# PBL44_Sch.net
KiCad netlist of a schematic drawn in Altium Designer
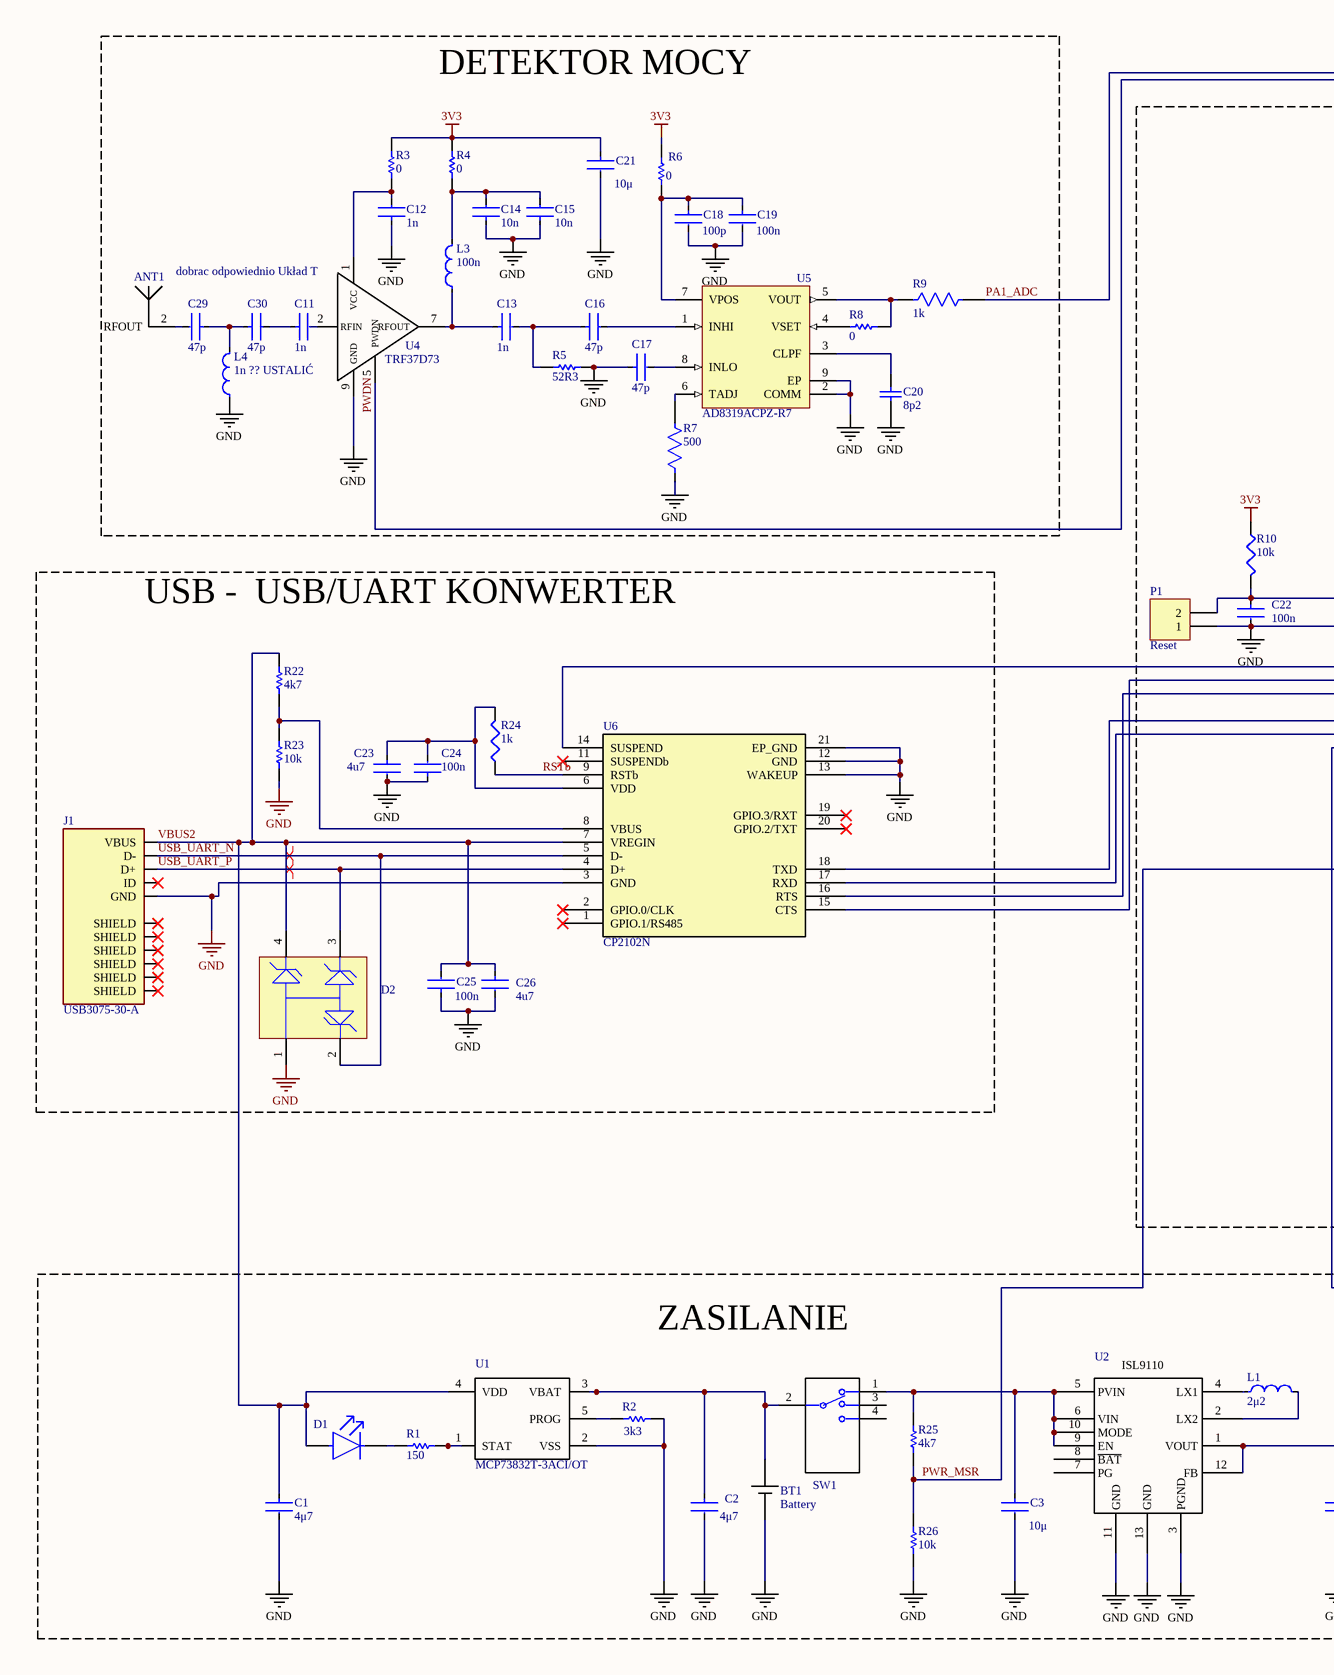
[diagram p0: PBL44_Sch.SchDoc, left]
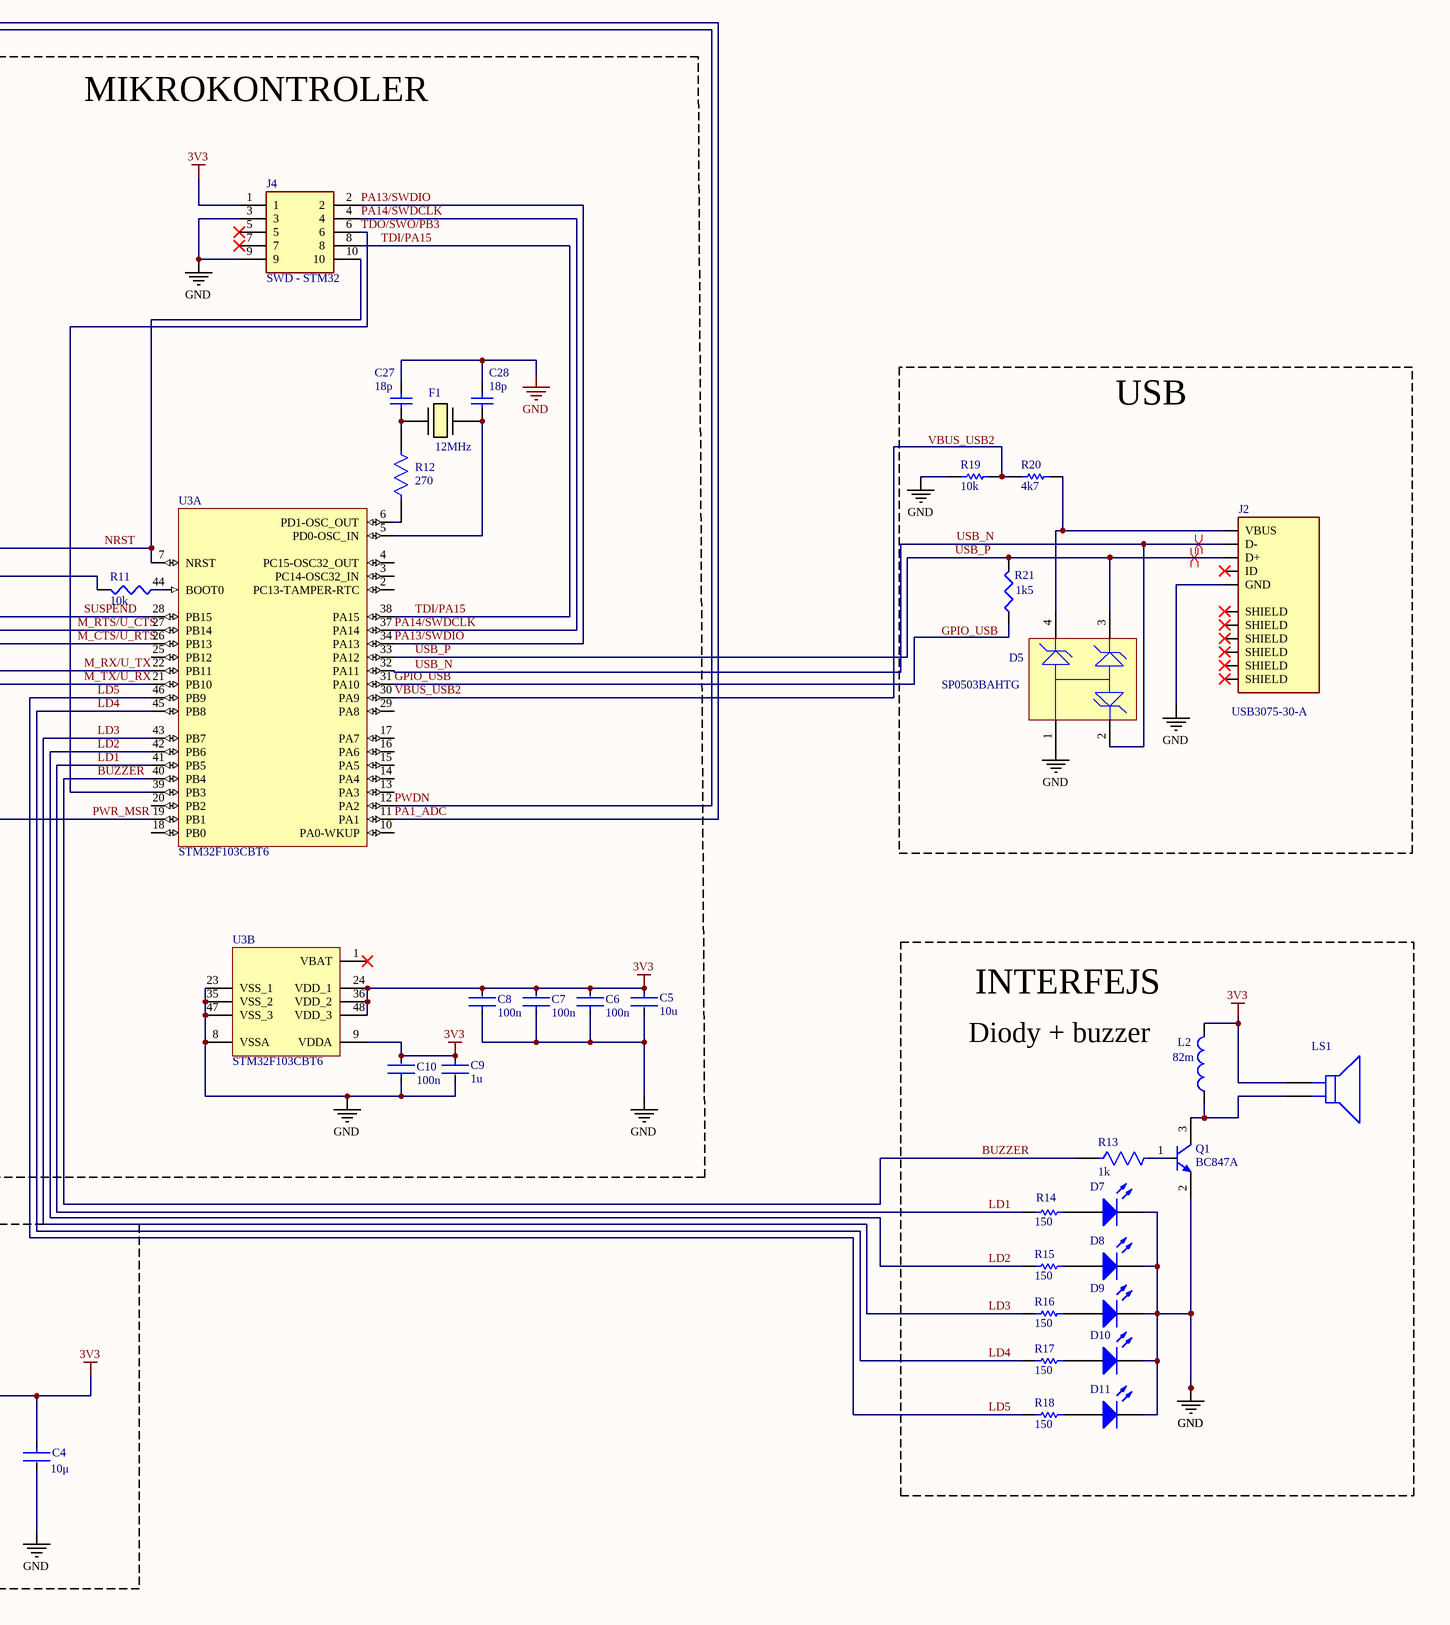
[diagram p1: PBL44_Sch.SchDoc, right]

(export (version "E")
  (design (tool "Eeschema 10.0.6"))
  (components
    (comp (ref "ANT1")
      (value "2195852-1")
      (footprint "Antena:Antena")
      (libsource (lib "Antena") (part "2195852-1"))
    )
    (comp (ref "BT1")
      (value "Battery")
      (footprint "PBL4_PCB_Lib:HDR1X2")
      (libsource (lib "Schlib_KM_PBL4") (part "KM_Battery_One_Cell"))
    )
    (comp (ref "C1")
      (value "~")
      (footprint "FP-C2012-125-0_2-IPC_B")
      (description "Multilayer Ceramic Capacitors 4.7μF ±10% 50V X5R SMD 0805")
      (fields
        (field (name "VOLTAGE") "50V")
        (field (name "CAPACITANCE") "4μ7")
        (field (name "TOLERANCE") "10%")
      )
      (libsource (lib "Altium Content Vault") (part "b4654b650e69147ec39a6b967a45e02"))
    )
    (comp (ref "C2")
      (value "~")
      (footprint "FP-C2012-125-0_2-IPC_B")
      (description "Multilayer Ceramic Capacitors 4.7μF ±10% 50V X5R SMD 0805")
      (fields
        (field (name "VOLTAGE") "50V")
        (field (name "CAPACITANCE") "4μ7")
        (field (name "TOLERANCE") "10%")
      )
      (libsource (lib "Altium Content Vault") (part "b4654b650e69147ec39a6b967a45e02"))
    )
    (comp (ref "C3")
      (value "10μ")
      (footprint "FP-C0805C-DG-MFG")
      (description "CAP CER 10UF 10V X5R 0805")
      (fields (field (name "TOLERANCE") "10%") (field (name "MANUFACTURER PART NUMBER") "C0805C106K8PACTU"))
      (libsource (lib "Altium Content Vault") (part "11868f565c42a9108669ba33697ecf6"))
    )
    (comp (ref "C4")
      (value "10μ")
      (footprint "FP-C0805C-DG-MFG")
      (description "CAP CER 10UF 10V X5R 0805")
      (fields (field (name "TOLERANCE") "10%") (field (name "MANUFACTURER PART NUMBER") "C0805C106K8PACTU"))
      (libsource (lib "Altium Content Vault") (part "11868f565c42a9108669ba33697ecf6"))
    )
    (comp (ref "C5")
      (value "10u")
      (footprint "FP-C0805C-DN-MFG")
      (description "CAP CER 47PF 100V 5% NP0 0805")
      (fields
        (field (name "MANUFACTURER") "KEMET")
        (field (name "OCTOPART") "https://octopart.com/c0805c470j1gactu-kemet-9138638")
      )
      (libsource (lib "Altium Content Vault") (part "b4654b650e69147ec39a6b967a45e02"))
    )
    (comp (ref "C6")
      (value "C0603C103K1RACTU")
      (footprint "FP-C0603C-CF-MFG")
      (description "CAP CER 10000PF 100V X7R 0603")
      (fields
        (field (name "MANUFACTURER") "KEMET")
        (field (name "CAPACITANCE") "100n")
        (field (name "OCTOPART") "https://octopart.com/c0603c103k1ractu-kemet-134140")
      )
      (libsource (lib "Altium Content Vault") (part "b4654b650e69147ec39a6b967a45e02"))
    )
    (comp (ref "C7")
      (value "C0603C103K1RACTU")
      (footprint "FP-C0603C-CF-MFG")
      (description "CAP CER 10000PF 100V X7R 0603")
      (fields
        (field (name "MANUFACTURER") "KEMET")
        (field (name "CAPACITANCE") "100n")
        (field (name "OCTOPART") "https://octopart.com/c0603c103k1ractu-kemet-134140")
      )
      (libsource (lib "Altium Content Vault") (part "b4654b650e69147ec39a6b967a45e02"))
    )
    (comp (ref "C8")
      (value "C0603C103K1RACTU")
      (footprint "FP-C0603C-CF-MFG")
      (description "CAP CER 10000PF 100V X7R 0603")
      (fields
        (field (name "MANUFACTURER") "KEMET")
        (field (name "CAPACITANCE") "100n")
        (field (name "OCTOPART") "https://octopart.com/c0603c103k1ractu-kemet-134140")
      )
      (libsource (lib "Altium Content Vault") (part "b4654b650e69147ec39a6b967a45e02"))
    )
    (comp (ref "C9")
      (value "1u")
      (footprint "FP-C0805C-DN-MFG")
      (description "CAP CER 47PF 100V 5% NP0 0805")
      (fields
        (field (name "MANUFACTURER") "KEMET")
        (field (name "OCTOPART") "https://octopart.com/c0805c470j1gactu-kemet-9138638")
      )
      (libsource (lib "Altium Content Vault") (part "b4654b650e69147ec39a6b967a45e02"))
    )
    (comp (ref "C10")
      (value "C0603C103K1RACTU")
      (footprint "FP-C0603C-CF-MFG")
      (description "CAP CER 10000PF 100V X7R 0603")
      (fields
        (field (name "MANUFACTURER") "KEMET")
        (field (name "CAPACITANCE") "100n")
        (field (name "OCTOPART") "https://octopart.com/c0603c103k1ractu-kemet-134140")
      )
      (libsource (lib "Altium Content Vault") (part "b4654b650e69147ec39a6b967a45e02"))
    )
    (comp (ref "C11")
      (value "06035C102KAT2A")
      (footprint "FP-0603-L_1_6_0_15-W_0_81-IPC_A")
      (description "General Purpose Ceramic Capacitor, 0603, 1nF, 10%, X7R, 15%, 50V")
      (fields
        (field (name "CAPACITANCE") "1n")
        (field (name "VOLTAGE") "50V")
        (field (name "TOLERANCE") "10%")
      )
      (libsource (lib "Altium Content Vault") (part "02cd4be3c70576c341d710602a673aa"))
    )
    (comp (ref "C12")
      (value "06035C102KAT2A")
      (footprint "FP-0603-L_1_6_0_15-W_0_81-IPC_A")
      (description "General Purpose Ceramic Capacitor, 0603, 1nF, 10%, X7R, 15%, 50V")
      (fields
        (field (name "CAPACITANCE") "1n")
        (field (name "VOLTAGE") "50V")
        (field (name "TOLERANCE") "10%")
      )
      (libsource (lib "Altium Content Vault") (part "02cd4be3c70576c341d710602a673aa"))
    )
    (comp (ref "C13")
      (value "06035C102KAT2A")
      (footprint "FP-0603-L_1_6_0_15-W_0_81-IPC_A")
      (description "General Purpose Ceramic Capacitor, 0603, 1nF, 10%, X7R, 15%, 50V")
      (fields
        (field (name "CAPACITANCE") "1n")
        (field (name "VOLTAGE") "50V")
        (field (name "TOLERANCE") "10%")
      )
      (libsource (lib "Altium Content Vault") (part "02cd4be3c70576c341d710602a673aa"))
    )
    (comp (ref "C14")
      (value "C0603C103K1RACTU")
      (footprint "FP-C0603C-CF-MFG")
      (description "CAP CER 10000PF 100V X7R 0603")
      (fields
        (field (name "MANUFACTURER") "KEMET")
        (field (name "CAPACITANCE") "10n")
        (field (name "OCTOPART") "https://octopart.com/c0603c103k1ractu-kemet-134140")
      )
      (libsource (lib "Altium Content Vault") (part "b4654b650e69147ec39a6b967a45e02"))
    )
    (comp (ref "C15")
      (value "C0603C103K1RACTU")
      (footprint "FP-C0603C-CF-MFG")
      (description "CAP CER 10000PF 100V X7R 0603")
      (fields
        (field (name "MANUFACTURER") "KEMET")
        (field (name "CAPACITANCE") "10n")
        (field (name "OCTOPART") "https://octopart.com/c0603c103k1ractu-kemet-134140")
      )
      (libsource (lib "Altium Content Vault") (part "b4654b650e69147ec39a6b967a45e02"))
    )
    (comp (ref "C16")
      (value "47p")
      (footprint "FP-C0805C-DN-MFG")
      (description "CAP CER 47PF 100V 5% NP0 0805")
      (fields
        (field (name "MANUFACTURER") "KEMET")
        (field (name "OCTOPART") "https://octopart.com/c0805c470j1gactu-kemet-9138638")
      )
      (libsource (lib "Altium Content Vault") (part "b4654b650e69147ec39a6b967a45e02"))
    )
    (comp (ref "C17")
      (value "47p")
      (footprint "FP-C0805C-DN-MFG")
      (description "CAP CER 47PF 100V 5% NP0 0805")
      (fields
        (field (name "MANUFACTURER") "KEMET")
        (field (name "OCTOPART") "https://octopart.com/c0805c470j1gactu-kemet-9138638")
      )
      (libsource (lib "Altium Content Vault") (part "b4654b650e69147ec39a6b967a45e02"))
    )
    (comp (ref "C18")
      (value "C0603C104K5RACTU")
      (footprint "FP-C0603C-CF-MFG")
      (description "CAP CER 0.1UF 50V X7R 0603")
      (fields
        (field (name "TOLERANCE") "0.1")
        (field (name "MANUFACTURER") "KEMET")
        (field (name "CAPACITANCE") "100p")
      )
      (libsource (lib "Altium Content Vault") (part "b4654b650e69147ec39a6b967a45e02"))
    )
    (comp (ref "C19")
      (value "C0603C104K5RACTU")
      (footprint "FP-C0603C-CF-MFG")
      (description "CAP CER 0.1UF 50V X7R 0603")
      (fields
        (field (name "TOLERANCE") "0.1")
        (field (name "MANUFACTURER") "KEMET")
        (field (name "CAPACITANCE") "100n")
      )
      (libsource (lib "Altium Content Vault") (part "b4654b650e69147ec39a6b967a45e02"))
    )
    (comp (ref "C20")
      (value "06035J8R2BBSTR")
      (footprint "CAPC1608X73X35ML10T15")
      (fields (field (name "MANUFACTURER") "AVX Interconnect / Elco") (field (name "CAPACITANCE") "8p2"))
      (libsource (lib "Altium Content Vault") (part "CAP"))
    )
    (comp (ref "C21")
      (value "10μ")
      (footprint "FP-C0805C-DG-MFG")
      (description "CAP CER 10UF 10V X5R 0805")
      (fields (field (name "TOLERANCE") "10%") (field (name "MANUFACTURER PART NUMBER") "C0805C106K8PACTU"))
      (libsource (lib "Altium Content Vault") (part "11868f565c42a9108669ba33697ecf6"))
    )
    (comp (ref "C22")
      (value "~")
      (footprint "FP-C2012-125-0_2-IPC_B")
      (description "Multilayer Ceramic Capacitors 4.7μF ±10% 50V X5R SMD 0805")
      (fields
        (field (name "VOLTAGE") "50V")
        (field (name "CAPACITANCE") "100n")
        (field (name "TOLERANCE") "10%")
      )
      (libsource (lib "Altium Content Vault") (part "b4654b650e69147ec39a6b967a45e02"))
    )
    (comp (ref "C23")
      (value "4u7")
      (footprint "FP-C0805C-DN-MFG")
      (description "CAP CER 47PF 100V 5% NP0 0805")
      (fields
        (field (name "MANUFACTURER") "KEMET")
        (field (name "OCTOPART") "https://octopart.com/c0805c470j1gactu-kemet-9138638")
      )
      (libsource (lib "Altium Content Vault") (part "b4654b650e69147ec39a6b967a45e02"))
    )
    (comp (ref "C24")
      (value "C0603C103K1RACTU")
      (footprint "FP-C0603C-CF-MFG")
      (description "CAP CER 10000PF 100V X7R 0603")
      (fields
        (field (name "MANUFACTURER") "KEMET")
        (field (name "CAPACITANCE") "100n")
        (field (name "OCTOPART") "https://octopart.com/c0603c103k1ractu-kemet-134140")
      )
      (libsource (lib "Altium Content Vault") (part "b4654b650e69147ec39a6b967a45e02"))
    )
    (comp (ref "C25")
      (value "C0603C103K1RACTU")
      (footprint "FP-C0603C-CF-MFG")
      (description "CAP CER 10000PF 100V X7R 0603")
      (fields
        (field (name "MANUFACTURER") "KEMET")
        (field (name "CAPACITANCE") "100n")
        (field (name "OCTOPART") "https://octopart.com/c0603c103k1ractu-kemet-134140")
      )
      (libsource (lib "Altium Content Vault") (part "b4654b650e69147ec39a6b967a45e02"))
    )
    (comp (ref "C26")
      (value "4u7")
      (footprint "FP-C0805C-DN-MFG")
      (description "CAP CER 47PF 100V 5% NP0 0805")
      (fields
        (field (name "MANUFACTURER") "KEMET")
        (field (name "OCTOPART") "https://octopart.com/c0805c470j1gactu-kemet-9138638")
      )
      (libsource (lib "Altium Content Vault") (part "b4654b650e69147ec39a6b967a45e02"))
    )
    (comp (ref "C27")
      (value "06035J8R2BBSTR")
      (footprint "CAPC1608X73X35ML10T15")
      (fields (field (name "MANUFACTURER") "AVX Interconnect / Elco") (field (name "CAPACITANCE") "18p"))
      (libsource (lib "Altium Content Vault") (part "CAP"))
    )
    (comp (ref "C28")
      (value "06035J8R2BBSTR")
      (footprint "CAPC1608X73X35ML10T15")
      (fields (field (name "MANUFACTURER") "AVX Interconnect / Elco") (field (name "CAPACITANCE") "18p"))
      (libsource (lib "Altium Content Vault") (part "CAP"))
    )
    (comp (ref "C29")
      (value "C0603C104K5RACTU")
      (footprint "FP-C0603C-CF-MFG")
      (description "CAP CER 0.1UF 50V X7R 0603")
      (fields
        (field (name "TOLERANCE") "0.1")
        (field (name "MANUFACTURER") "KEMET")
        (field (name "CAPACITANCE") "47p")
      )
      (libsource (lib "Altium Content Vault") (part "b4654b650e69147ec39a6b967a45e02"))
    )
    (comp (ref "C30")
      (value "C0603C104K5RACTU")
      (footprint "FP-C0603C-CF-MFG")
      (description "CAP CER 0.1UF 50V X7R 0603")
      (fields
        (field (name "TOLERANCE") "0.1")
        (field (name "MANUFACTURER") "KEMET")
        (field (name "CAPACITANCE") "47p")
      )
      (libsource (lib "Altium Content Vault") (part "b4654b650e69147ec39a6b967a45e02"))
    )
    (comp (ref "D1")
      (value "LTST-C190GKT")
      (footprint "FP-LTST-C190GKT-MFG")
      (description "LED GREEN CLEAR CHIP SMD")
      (fields (field (name "VOLTAGE") "2V"))
      (libsource (lib "Altium Content Vault") (part "8706943c75ba83719d021d2fdc84c58"))
    )
    (comp (ref "D2")
      (value "SP0503BAHTG")
      (footprint "LFUS-SOT143-4_V")
      (description "TVS Diode Array, 30 pF, 30 KV, -40 to 85 degC, 4-Pin SOT143, RoHS, Tape and Reel")
      (fields (field (name "MANUFACTURER") "Littelfuse"))
      (libsource (lib "Altium Content Vault") (part "LFUS-SP0503BAHTG-SOT143-4"))
    )
    (comp (ref "D5")
      (value "SP0503BAHTG")
      (footprint "LFUS-SOT143-4_V")
      (description "TVS Diode Array, 30 pF, 30 KV, -40 to 85 degC, 4-Pin SOT143, RoHS, Tape and Reel")
      (fields (field (name "MANUFACTURER") "Littelfuse"))
      (libsource (lib "Altium Content Vault") (part "LFUS-SP0503BAHTG-SOT143-4"))
    )
    (comp (ref "D7")
      (value "151051RS11000")
      (footprint "Type 5mm")
      (description "THT LED round mono-color color lens, WL-TMRW, Red")
      (fields (field (name "MANUFACTURER") "Wuerth Elektronik"))
      (libsource (lib "Altium Content Vault") (part "WE-LED_K1A2-2"))
    )
    (comp (ref "D8")
      (value "151051RS11000")
      (footprint "Type 5mm")
      (description "THT LED round mono-color color lens, WL-TMRW, Red")
      (fields (field (name "MANUFACTURER") "Wuerth Elektronik"))
      (libsource (lib "Altium Content Vault") (part "WE-LED_K1A2-2"))
    )
    (comp (ref "D9")
      (value "151051RS11000")
      (footprint "Type 5mm")
      (description "THT LED round mono-color color lens, WL-TMRW, Red")
      (fields (field (name "MANUFACTURER") "Wuerth Elektronik"))
      (libsource (lib "Altium Content Vault") (part "WE-LED_K1A2-2"))
    )
    (comp (ref "D10")
      (value "151051RS11000")
      (footprint "Type 5mm")
      (description "THT LED round mono-color color lens, WL-TMRW, Red")
      (fields (field (name "MANUFACTURER") "Wuerth Elektronik"))
      (libsource (lib "Altium Content Vault") (part "WE-LED_K1A2-2"))
    )
    (comp (ref "D11")
      (value "151051RS11000")
      (footprint "Type 5mm")
      (description "THT LED round mono-color color lens, WL-TMRW, Red")
      (fields (field (name "MANUFACTURER") "Wuerth Elektronik"))
      (libsource (lib "Altium Content Vault") (part "WE-LED_K1A2-2"))
    )
    (comp (ref "F1")
      (value "12MHz")
      (footprint "AltiumLibraryElements:HC/49US-(AT49)_1")
      (fields
        (field (name "MANUFACTURER_PART_NUMBER") "ABLS-12.000MHZ-B4-T")
        (field (name "MOUSER PART NUMBER") "815-ABLS-12.0M-T")
      )
      (libsource (lib "AltiumLibraryElements") (part "ABLS-12.000MHZ-B4-T"))
    )
    (comp (ref "J1")
      (value "USB3075-30-A")
      (footprint "PBL4_PCB_Lib:GCT_USB3075-30-A")
      (description "USB - micro B USB 2.0 Receptacle Connector 5 Position Surface Mount, Right Angle; Through Hole")
      (fields
        (field (name "MF") "Global Connector Technology")
        (field (name "DIGI-KEY_PART_NUMBER") "2073-USB3075-30-ACT-ND")
      )
      (libsource (lib "USB3075-30-A") (part "USB3075-30-A"))
    )
    (comp (ref "J2")
      (value "USB3075-30-A")
      (footprint "PBL4_PCB_Lib:GCT_USB3075-30-A")
      (description "USB - micro B USB 2.0 Receptacle Connector 5 Position Surface Mount, Right Angle; Through Hole")
      (fields
        (field (name "MF") "Global Connector Technology")
        (field (name "DIGI-KEY_PART_NUMBER") "2073-USB3075-30-ACT-ND")
      )
      (libsource (lib "") (part "USB3075-30-A_1"))
    )
    (comp (ref "J4")
      (value "SWD - STM32")
      (footprint "PBL4_PCB_Lib:322110030000")
      (description "Connector")
      (fields (field (name "MANUFACTURER_PART_NUMBER") "3221-10-0300-00"))
      (libsource (lib "AltiumLibraryElements") (part "3221-10-0300-00"))
    )
    (comp (ref "L1")
      (value "NRS5040T2R2NMGJ")
      (footprint "FP-NR5040-H_4_1-MFG")
      (description "SMD Power Inductors 2.2uH ±30% 3.7A 28.6mΩ")
      (fields (field (name "TOLERANCE") "20%") (field (name "INDUCTANCE") "2μ2"))
      (libsource (lib "Altium Content Vault") (part "725321dda6339637d4d059423bc1c3c"))
    )
    (comp (ref "L2")
      (value "7447471104")
      (footprint "WE-TIS 1111")
      (description "Shielded Radial Leaded Wire Wound Inductor WE-TIS, L=100000 µH")
      (fields (field (name "INDUCTANCE") "82m") (field (name "MANUFACTURER") "Wuerth Elektronik"))
      (libsource (lib "Altium Content Vault") (part "PAS-IND-INDUCTOR-2"))
    )
    (comp (ref "L3")
      (value "LQW18ANR10G00D")
      (footprint "FP-LQW18AN_00-MFG")
      (description "Wire Wound RF Inductor 100nH ±2% 220mA 0.68Ω 0603 (1608)")
      (fields (field (name "TOLERANCE") "2%") (field (name "INDUCTANCE") "100n"))
      (libsource (lib "Altium Content Vault") (part "725321dda6339637d4d059423bc1c3c"))
    )
    (comp (ref "L4")
      (value "LQW18ANR10G00D")
      (footprint "FP-LQW18AN_00-MFG")
      (description "Wire Wound RF Inductor 100nH ±2% 220mA 0.68Ω 0603 (1608)")
      (fields (field (name "TOLERANCE") "2%") (field (name "INDUCTANCE") "1n ?? USTALIĆ"))
      (libsource (lib "Altium Content Vault") (part "725321dda6339637d4d059423bc1c3c"))
    )
    (comp (ref "LS1")
      (value "7BB-20-6L0")
      (footprint "FP-7BB-20-6L0-MFG")
      (description "BUZZER ELEMENT STD 6.3KHZ")
      (libsource (lib "Components - 08.04.22 - 12.49") (part "CMP-06202-000037-1"))
    )
    (comp (ref "P1")
      (value "Reset")
      (footprint "HDR1X2")
      (description "Header, 2-Pin")
      (fields (field (name "PUBLISHER") "Altium Limited"))
      (libsource (lib "Miscellaneous Connectors") (part "Header 2"))
    )
    (comp (ref "Q1")
      (value "BC847A")
      (footprint "INF-SOT23_M")
      (description "NPN Silicon AF Transistor, 45 V VCEO, 100 mA IC, SOT23, Reel, Green")
      (fields (field (name "MANUFACTURER") "Infineon"))
      (libsource (lib "Altium Content Vault") (part "INF-BJTNPN-BEC-3"))
    )
    (comp (ref "R1")
      (value "ERJ-3EKF4700V")
      (footprint "RESC1608X55X30ML15T15")
      (description "Chip Resistor, 470 Ohm, +/- 1%, 0.1 W, -55 to 155 degC, 0603 (1608 Metric), RoHS, Tape and Reel")
      (fields (field (name "MANUFACTURER") "Panasonic") (field (name "RESISTANCE") "150"))
      (libsource (lib "Altium Content Vault") (part "RES-2"))
    )
    (comp (ref "R2")
      (value "RC0805FR-073K3L")
      (footprint "RESC2013X60X35ML10T20")
      (description "Chip Resistor, 3.3 KOhm, +/- 1%, 0.125 W, -55 to 155 degC, 0805 (2012 Metric), RoHS, Tape and Reel")
      (fields
        (field (name "RESISTANCE") "3k3")
        (field (name "TOLERANCE") "1%")
        (field (name "MANUFACTURER") "Yageo")
      )
      (libsource (lib "Altium Content Vault") (part "RES-2"))
    )
    (comp (ref "R3")
      (value "0")
      (footprint "RESC1609X50X30NL8T20")
      (description "Chip Resistor, 0 Ohm, Jumper, 100 mW, -55 to 155 degC, 0603 (1608 Metric), RoHS, Tape and Reel")
      (fields
        (field (name "MANUFACTURER") "Vishay Semiconductor")
        (field (name "Comment") "CRCW06030000Z0EA")
      )
      (libsource (lib "Altium Content Vault") (part "RES-2"))
    )
    (comp (ref "R4")
      (value "0")
      (footprint "RESC1609X50X30NL8T20")
      (description "Chip Resistor, 0 Ohm, Jumper, 100 mW, -55 to 155 degC, 0603 (1608 Metric), RoHS, Tape and Reel")
      (fields
        (field (name "MANUFACTURER") "Vishay Semiconductor")
        (field (name "Comment") "CRCW06030000Z0EA")
      )
      (libsource (lib "Altium Content Vault") (part "RES-2"))
    )
    (comp (ref "R5")
      (value "ERJ-3EKF52R3V")
      (footprint "RESC1608X55X30ML15T15")
      (fields (field (name "MANUFACTURER") "Panasonic") (field (name "RESISTANCE") "52R3"))
      (libsource (lib "Altium Content Vault") (part "RES"))
    )
    (comp (ref "R6")
      (value "CRCW06030000Z0EA")
      (footprint "RESC1609X50X30NL8T20")
      (description "Chip Resistor, 0 Ohm, Jumper, 100 mW, -55 to 155 degC, 0603 (1608 Metric), RoHS, Tape and Reel")
      (fields (field (name "MANUFACTURER") "Vishay Semiconductor") (field (name "RESISTANCE") "0"))
      (libsource (lib "Altium Content Vault") (part "RES-2"))
    )
    (comp (ref "R7")
      (value "MCT06030D5000BP100")
      (footprint "FP-MCT0603-MFG")
      (description "RES SMD 100 OHM 1% 1/8W 0603")
      (fields (field (name "RESISTANCE") "500") (field (name "TOLERANCE") "0.1%"))
      (libsource (lib "Altium Content Vault") (part "1029c3af85768c4190bb7ad29bc67b5"))
    )
    (comp (ref "R8")
      (value "CRCW06030000Z0EA")
      (footprint "RESC1609X50X30NL8T20")
      (description "Chip Resistor, 0 Ohm, Jumper, 100 mW, -55 to 155 degC, 0603 (1608 Metric), RoHS, Tape and Reel")
      (fields (field (name "MANUFACTURER") "Vishay Semiconductor") (field (name "RESISTANCE") "0"))
      (libsource (lib "Altium Content Vault") (part "RES-2"))
    )
    (comp (ref "R9")
      (value "CRCW06031K00FKEA")
      (footprint "FP-CRCW0603-e3-MFG")
      (description "RES Thick Film, 1kΩ, 1%, 0.1W, 100ppm/°C, 0603")
      (fields (field (name "TOLERANCE") "1%") (field (name "RESISTANCE") "1k"))
      (libsource (lib "Altium Content Vault") (part "1029c3af85768c4190bb7ad29bc67b5"))
    )
    (comp (ref "R10")
      (value "10k")
      (footprint "J1-0603")
      (description "Resistor")
      (fields (field (name "Comment") "Res3") (field (name "PUBLISHER") "Altium Limited"))
      (libsource (lib "Miscellaneous Devices") (part "Res3"))
    )
    (comp (ref "R11")
      (value "10k")
      (footprint "J1-0603")
      (description "Resistor")
      (fields (field (name "Comment") "Res3") (field (name "PUBLISHER") "Altium Limited"))
      (libsource (lib "Miscellaneous Devices") (part "Res3"))
    )
    (comp (ref "R12")
      (value "CRCW06031K00FKEA")
      (footprint "FP-CRCW0603-e3-MFG")
      (description "RES Thick Film, 1kΩ, 1%, 0.1W, 100ppm/°C, 0603")
      (fields (field (name "TOLERANCE") "1%") (field (name "RESISTANCE") "270"))
      (libsource (lib "Altium Content Vault") (part "1029c3af85768c4190bb7ad29bc67b5"))
    )
    (comp (ref "R13")
      (value "CRCW06031K00FKEA")
      (footprint "FP-CRCW0603-e3-MFG")
      (description "RES Thick Film, 1kΩ, 1%, 0.1W, 100ppm/°C, 0603")
      (fields (field (name "TOLERANCE") "1%") (field (name "RESISTANCE") "1k"))
      (libsource (lib "Altium Content Vault") (part "1029c3af85768c4190bb7ad29bc67b5"))
    )
    (comp (ref "R14")
      (value "ERJ-3EKF4700V")
      (footprint "RESC1608X55X30ML15T15")
      (description "Chip Resistor, 470 Ohm, +/- 1%, 0.1 W, -55 to 155 degC, 0603 (1608 Metric), RoHS, Tape and Reel")
      (fields (field (name "MANUFACTURER") "Panasonic") (field (name "RESISTANCE") "150"))
      (libsource (lib "Altium Content Vault") (part "RES-2"))
    )
    (comp (ref "R15")
      (value "ERJ-3EKF4700V")
      (footprint "RESC1608X55X30ML15T15")
      (description "Chip Resistor, 470 Ohm, +/- 1%, 0.1 W, -55 to 155 degC, 0603 (1608 Metric), RoHS, Tape and Reel")
      (fields (field (name "MANUFACTURER") "Panasonic") (field (name "RESISTANCE") "150"))
      (libsource (lib "Altium Content Vault") (part "RES-2"))
    )
    (comp (ref "R16")
      (value "ERJ-3EKF4700V")
      (footprint "RESC1608X55X30ML15T15")
      (description "Chip Resistor, 470 Ohm, +/- 1%, 0.1 W, -55 to 155 degC, 0603 (1608 Metric), RoHS, Tape and Reel")
      (fields (field (name "MANUFACTURER") "Panasonic") (field (name "RESISTANCE") "150"))
      (libsource (lib "Altium Content Vault") (part "RES-2"))
    )
    (comp (ref "R17")
      (value "ERJ-3EKF4700V")
      (footprint "RESC1608X55X30ML15T15")
      (description "Chip Resistor, 470 Ohm, +/- 1%, 0.1 W, -55 to 155 degC, 0603 (1608 Metric), RoHS, Tape and Reel")
      (fields (field (name "MANUFACTURER") "Panasonic") (field (name "RESISTANCE") "150"))
      (libsource (lib "Altium Content Vault") (part "RES-2"))
    )
    (comp (ref "R18")
      (value "ERJ-3EKF4700V")
      (footprint "RESC1608X55X30ML15T15")
      (description "Chip Resistor, 470 Ohm, +/- 1%, 0.1 W, -55 to 155 degC, 0603 (1608 Metric), RoHS, Tape and Reel")
      (fields (field (name "MANUFACTURER") "Panasonic") (field (name "RESISTANCE") "150"))
      (libsource (lib "Altium Content Vault") (part "RES-2"))
    )
    (comp (ref "R19")
      (value "RC0805FR-073K3L")
      (footprint "RESC2013X60X35ML10T20")
      (description "Chip Resistor, 3.3 KOhm, +/- 1%, 0.125 W, -55 to 155 degC, 0805 (2012 Metric), RoHS, Tape and Reel")
      (fields
        (field (name "RESISTANCE") "10k")
        (field (name "TOLERANCE") "1%")
        (field (name "MANUFACTURER") "Yageo")
      )
      (libsource (lib "Altium Content Vault") (part "RES-2"))
    )
    (comp (ref "R20")
      (value "RC0805FR-073K3L")
      (footprint "RESC2013X60X35ML10T20")
      (description "Chip Resistor, 3.3 KOhm, +/- 1%, 0.125 W, -55 to 155 degC, 0805 (2012 Metric), RoHS, Tape and Reel")
      (fields
        (field (name "RESISTANCE") "4k7")
        (field (name "TOLERANCE") "1%")
        (field (name "MANUFACTURER") "Yageo")
      )
      (libsource (lib "Altium Content Vault") (part "RES-2"))
    )
    (comp (ref "R21")
      (value "1k5")
      (footprint "J1-0603")
      (description "Resistor")
      (fields (field (name "Comment") "Res3") (field (name "PUBLISHER") "Altium Limited"))
      (libsource (lib "Miscellaneous Devices") (part "Res3"))
    )
    (comp (ref "R22")
      (value "RC0805FR-073K3L")
      (footprint "RESC2013X60X35ML10T20")
      (description "Chip Resistor, 3.3 KOhm, +/- 1%, 0.125 W, -55 to 155 degC, 0805 (2012 Metric), RoHS, Tape and Reel")
      (fields
        (field (name "RESISTANCE") "4k7")
        (field (name "TOLERANCE") "1%")
        (field (name "MANUFACTURER") "Yageo")
      )
      (libsource (lib "Altium Content Vault") (part "RES-2"))
    )
    (comp (ref "R23")
      (value "RC0805FR-073K3L")
      (footprint "RESC2013X60X35ML10T20")
      (description "Chip Resistor, 3.3 KOhm, +/- 1%, 0.125 W, -55 to 155 degC, 0805 (2012 Metric), RoHS, Tape and Reel")
      (fields
        (field (name "RESISTANCE") "10k")
        (field (name "TOLERANCE") "1%")
        (field (name "MANUFACTURER") "Yageo")
      )
      (libsource (lib "Altium Content Vault") (part "RES-2"))
    )
    (comp (ref "R24")
      (value "1k")
      (footprint "J1-0603")
      (description "Resistor")
      (fields (field (name "Comment") "Res3") (field (name "PUBLISHER") "Altium Limited"))
      (libsource (lib "Miscellaneous Devices") (part "Res3"))
    )
    (comp (ref "R25")
      (value "RC0805FR-073K3L")
      (footprint "RESC2013X60X35ML10T20")
      (description "Chip Resistor, 3.3 KOhm, +/- 1%, 0.125 W, -55 to 155 degC, 0805 (2012 Metric), RoHS, Tape and Reel")
      (fields
        (field (name "RESISTANCE") "4k7")
        (field (name "TOLERANCE") "1%")
        (field (name "MANUFACTURER") "Yageo")
      )
      (libsource (lib "Altium Content Vault") (part "RES-2"))
    )
    (comp (ref "R26")
      (value "RC0805FR-073K3L")
      (footprint "RESC2013X60X35ML10T20")
      (description "Chip Resistor, 3.3 KOhm, +/- 1%, 0.125 W, -55 to 155 degC, 0805 (2012 Metric), RoHS, Tape and Reel")
      (fields
        (field (name "RESISTANCE") "10k")
        (field (name "TOLERANCE") "1%")
        (field (name "MANUFACTURER") "Yageo")
      )
      (libsource (lib "Altium Content Vault") (part "RES-2"))
    )
    (comp (ref "SW1")
      (value "MHS133G04")
      (footprint "PBL4_PCB_Lib:Alcoswitch_MHS133G04_0")
      (libsource (lib "Switch_Alcoswitch_MHS133G04_eec") (part "MHS133G04"))
    )
    (comp (ref "U1")
      (value "MCP73832T-3ACI/OT")
      (footprint "SOT-23-OT5_M")
      (libsource (lib "Components - 19.03.22 - 12.24") (part "CMP-0133-00135-1"))
    )
    (comp (ref "U2")
      (value "ISL9110")
      (footprint "KM_L12.3x3C")
      (description "L12.3x3C")
      (libsource (lib "Schlib_KM_PBL4") (part "KM_ISL9110"))
    )
    (comp (ref "U3")
      (value "STM32F103CBT6")
      (footprint "STM-LQFP48_L")
      (libsource (lib "Altium Content Vault") (part "MC-ARM-STM32F103X8_B-SQ48"))
    )
    (comp (ref "U4")
      (value "TRF37D73")
      (footprint "JD_WSON-8")
      (libsource (lib "JD_Projekt") (part "JD_TRF37D73_WSON-8"))
    )
    (comp (ref "U5")
      (value "AD8319ACPZ-R7")
      (footprint "ADI-CP-8-1_L")
      (description "1 MHz to 10 GHz, 45 dB Log Detector/Controller, 6ns Response Time, CP-8-1, Pb-Free, 3000 Reel")
      (libsource (lib "Components - 10.04.22 - 23.39") (part "CMP-0284-00069-1"))
    )
    (comp (ref "U6")
      (value "CP2102N")
      (footprint "PBL4_PCB_Lib:ZW_QFN20")
      (libsource (lib "PBL4_ZW") (part "ZW_CP2102N-A02-GQFN20R"))
    )
  )
  (nets
    (net (code "1") (name "/BUZZER") (class "Default")
      (node (ref "R13") (pin "1") (pinfunction "1_1") (pintype "passive"))
      (node (ref "U3") (pin "40") (pinfunction "PB4_40") (pintype "bidirectional"))
    )
    (net (code "2") (name "/GPIO_USB") (class "Default")
      (node (ref "R21") (pin "1") (pinfunction "1_1") (pintype "passive"))
      (node (ref "U3") (pin "31") (pinfunction "PA10_31") (pintype "bidirectional"))
    )
    (net (code "3") (name "/LD1") (class "Default")
      (node (ref "R14") (pin "1") (pinfunction "1_1") (pintype "passive"))
      (node (ref "U3") (pin "41") (pinfunction "PB5_41") (pintype "bidirectional"))
    )
    (net (code "4") (name "/LD2") (class "Default")
      (node (ref "R15") (pin "1") (pinfunction "1_1") (pintype "passive"))
      (node (ref "U3") (pin "42") (pinfunction "PB6_42") (pintype "bidirectional"))
    )
    (net (code "5") (name "/LD3") (class "Default")
      (node (ref "R16") (pin "1") (pinfunction "1_1") (pintype "passive"))
      (node (ref "U3") (pin "43") (pinfunction "PB7_43") (pintype "bidirectional"))
    )
    (net (code "6") (name "/LD4") (class "Default")
      (node (ref "R17") (pin "1") (pinfunction "1_1") (pintype "passive"))
      (node (ref "U3") (pin "45") (pinfunction "PB8_45") (pintype "bidirectional"))
    )
    (net (code "7") (name "/LD5") (class "Default")
      (node (ref "R18") (pin "1") (pinfunction "1_1") (pintype "passive"))
      (node (ref "U3") (pin "46") (pinfunction "PB9_46") (pintype "bidirectional"))
    )
    (net (code "8") (name "/M_CTS{slash}U_RTS") (class "Default")
      (node (ref "U3") (pin "26") (pinfunction "PB13_26") (pintype "bidirectional"))
      (node (ref "U6") (pin "16") (pinfunction "RTS_16") (pintype "passive"))
    )
    (net (code "9") (name "/M_RTS{slash}U_CTS") (class "Default")
      (node (ref "U3") (pin "27") (pinfunction "PB14_27") (pintype "bidirectional"))
      (node (ref "U6") (pin "15") (pinfunction "CTS_15") (pintype "passive"))
    )
    (net (code "10") (name "/M_RX{slash}U_TX") (class "Default")
      (node (ref "U3") (pin "22") (pinfunction "PB11_22") (pintype "bidirectional"))
      (node (ref "U6") (pin "18") (pinfunction "TXD_18") (pintype "passive"))
    )
    (net (code "11") (name "/M_TX{slash}U_RX") (class "Default")
      (node (ref "U3") (pin "21") (pinfunction "PB10_21") (pintype "bidirectional"))
      (node (ref "U6") (pin "17") (pinfunction "RXD_17") (pintype "passive"))
    )
    (net (code "12") (name "/NRST") (class "Default")
      (node (ref "C22") (pin "1") (pinfunction "1_1") (pintype "passive"))
      (node (ref "J4") (pin "10") (pinfunction "10_10") (pintype "passive"))
      (node (ref "P1") (pin "2") (pinfunction "2_2") (pintype "passive"))
      (node (ref "R10") (pin "2") (pinfunction "2_2") (pintype "passive"))
      (node (ref "U3") (pin "7") (pinfunction "NRST_7") (pintype "bidirectional"))
    )
    (net (code "13") (name "/PA1_ADC") (class "Default")
      (node (ref "R9") (pin "2") (pinfunction "2_2") (pintype "passive"))
      (node (ref "U3") (pin "11") (pinfunction "PA1_11") (pintype "bidirectional"))
    )
    (net (code "14") (name "/PA13{slash}SWDIO") (class "Default")
      (node (ref "J4") (pin "2") (pinfunction "2_2") (pintype "passive"))
      (node (ref "U3") (pin "34") (pinfunction "PA13_34") (pintype "bidirectional"))
    )
    (net (code "15") (name "/PA14{slash}SWDCLK") (class "Default")
      (node (ref "J4") (pin "4") (pinfunction "4_4") (pintype "passive"))
      (node (ref "U3") (pin "37") (pinfunction "PA14_37") (pintype "bidirectional"))
    )
    (net (code "16") (name "/PWDN") (class "Default")
      (node (ref "U3") (pin "12") (pinfunction "PA2_12") (pintype "bidirectional"))
      (node (ref "U4") (pin "5") (pinfunction "PWDN_5") (pintype "passive"))
    )
    (net (code "17") (name "/PWR_MSR") (class "Default")
      (node (ref "R25") (pin "2") (pinfunction "2_2") (pintype "passive"))
      (node (ref "R26") (pin "1") (pinfunction "1_1") (pintype "passive"))
      (node (ref "U3") (pin "19") (pinfunction "PB1_19") (pintype "bidirectional"))
    )
    (net (code "18") (name "/RSTb") (class "Default")
      (node (ref "R24") (pin "2") (pinfunction "2_2") (pintype "passive"))
      (node (ref "U6") (pin "9") (pinfunction "RSTb_9") (pintype "passive"))
    )
    (net (code "19") (name "/SUSPEND") (class "Default")
      (node (ref "U3") (pin "28") (pinfunction "PB15_28") (pintype "bidirectional"))
      (node (ref "U6") (pin "14") (pinfunction "SUSPEND_14") (pintype "passive"))
    )
    (net (code "20") (name "/TDI{slash}PA15") (class "Default")
      (node (ref "J4") (pin "8") (pinfunction "8_8") (pintype "passive"))
      (node (ref "U3") (pin "38") (pinfunction "PA15_38") (pintype "bidirectional"))
    )
    (net (code "21") (name "/TDO{slash}SWO{slash}PB3") (class "Default")
      (node (ref "J4") (pin "6") (pinfunction "6_6") (pintype "passive"))
      (node (ref "U3") (pin "39") (pinfunction "PB3_39") (pintype "bidirectional"))
    )
    (net (code "22") (name "/USB_N") (class "Default")
      (node (ref "D5") (pin "2") (pinfunction "2_2") (pintype "passive"))
      (node (ref "J2") (pin "2") (pinfunction "D-_2") (pintype "bidirectional"))
      (node (ref "U3") (pin "32") (pinfunction "PA11_32") (pintype "bidirectional"))
    )
    (net (code "23") (name "/USB_P") (class "Default")
      (node (ref "D5") (pin "3") (pinfunction "3_3") (pintype "passive"))
      (node (ref "J2") (pin "3") (pinfunction "D+_3") (pintype "bidirectional"))
      (node (ref "R21") (pin "2") (pinfunction "2_2") (pintype "passive"))
      (node (ref "U3") (pin "33") (pinfunction "PA12_33") (pintype "bidirectional"))
    )
    (net (code "24") (name "/USB_UART_N") (class "Default")
      (node (ref "D2") (pin "2") (pinfunction "2_2") (pintype "passive"))
      (node (ref "J1") (pin "2") (pinfunction "D-_2") (pintype "bidirectional"))
      (node (ref "U6") (pin "5") (pinfunction "D-_5") (pintype "passive"))
    )
    (net (code "25") (name "/USB_UART_P") (class "Default")
      (node (ref "D2") (pin "3") (pinfunction "3_3") (pintype "passive"))
      (node (ref "J1") (pin "3") (pinfunction "D+_3") (pintype "bidirectional"))
      (node (ref "U6") (pin "4") (pinfunction "D+_4") (pintype "passive"))
    )
    (net (code "26") (name "/VBUS2") (class "Default")
      (node (ref "C1") (pin "1") (pinfunction "1_1") (pintype "passive"))
      (node (ref "C25") (pin "2") (pinfunction "2_2") (pintype "passive"))
      (node (ref "C26") (pin "1") (pinfunction "1_1") (pintype "passive"))
      (node (ref "D1") (pin "2") (pinfunction "A_2") (pintype "passive"))
      (node (ref "D2") (pin "4") (pinfunction "4_4") (pintype "passive"))
      (node (ref "J1") (pin "1") (pinfunction "VBUS_1") (pintype "power_in"))
      (node (ref "R22") (pin "2") (pinfunction "2_2") (pintype "passive"))
      (node (ref "U1") (pin "4") (pinfunction "VDD_4") (pintype "power_in"))
      (node (ref "U6") (pin "7") (pinfunction "VREGIN_7") (pintype "passive"))
    )
    (net (code "27") (name "/VBUS_USB2") (class "Default")
      (node (ref "R19") (pin "1") (pinfunction "1_1") (pintype "passive"))
      (node (ref "R20") (pin "2") (pinfunction "2_2") (pintype "passive"))
      (node (ref "U3") (pin "30") (pinfunction "PA9_30") (pintype "bidirectional"))
    )
    (net (code "28") (name "3V3") (class "Default")
      (node (ref "C10") (pin "2") (pinfunction "2_2") (pintype "passive"))
      (node (ref "C21") (pin "1") (pinfunction "1_1") (pintype "passive"))
      (node (ref "C4") (pin "1") (pinfunction "1_1") (pintype "passive"))
      (node (ref "C5") (pin "1") (pinfunction "1_1") (pintype "passive"))
      (node (ref "C6") (pin "2") (pinfunction "2_2") (pintype "passive"))
      (node (ref "C7") (pin "2") (pinfunction "2_2") (pintype "passive"))
      (node (ref "C8") (pin "2") (pinfunction "2_2") (pintype "passive"))
      (node (ref "C9") (pin "1") (pinfunction "1_1") (pintype "passive"))
      (node (ref "J4") (pin "1") (pinfunction "1_1") (pintype "passive"))
      (node (ref "L2") (pin "2") (pinfunction "2_2") (pintype "passive"))
      (node (ref "LS1") (pin "17") (pinfunction "17_17") (pintype "passive"))
      (node (ref "R10") (pin "1") (pinfunction "1_1") (pintype "passive"))
      (node (ref "R3") (pin "2") (pinfunction "2_2") (pintype "passive"))
      (node (ref "R4") (pin "2") (pinfunction "2_2") (pintype "passive"))
      (node (ref "R6") (pin "2") (pinfunction "2_2") (pintype "passive"))
      (node (ref "U2") (pin "1") (pinfunction "VOUT_1") (pintype "passive"))
      (node (ref "U2") (pin "12") (pinfunction "FB_12") (pintype "passive"))
      (node (ref "U3") (pin "24") (pinfunction "VDD_1_24") (pintype "power_in"))
      (node (ref "U3") (pin "36") (pinfunction "VDD_2_36") (pintype "power_in"))
      (node (ref "U3") (pin "48") (pinfunction "VDD_3_48") (pintype "power_in"))
      (node (ref "U3") (pin "9") (pinfunction "VDDA_9") (pintype "power_in"))
    )
    (net (code "29") (name "GND") (class "Default")
      (node (ref "BT1") (pin "1") (pinfunction "1_1") (pintype "passive"))
      (node (ref "C1") (pin "2") (pinfunction "2_2") (pintype "passive"))
      (node (ref "C10") (pin "1") (pinfunction "1_1") (pintype "passive"))
      (node (ref "C12") (pin "1") (pinfunction "1_1") (pintype "passive"))
      (node (ref "C14") (pin "1") (pinfunction "1_1") (pintype "passive"))
      (node (ref "C15") (pin "1") (pinfunction "1_1") (pintype "passive"))
      (node (ref "C17") (pin "1") (pinfunction "1_1") (pintype "passive"))
      (node (ref "C18") (pin "2") (pinfunction "2_2") (pintype "passive"))
      (node (ref "C19") (pin "2") (pinfunction "2_2") (pintype "passive"))
      (node (ref "C2") (pin "2") (pinfunction "2_2") (pintype "passive"))
      (node (ref "C20") (pin "1") (pinfunction "1_1") (pintype "passive"))
      (node (ref "C21") (pin "2") (pinfunction "2_2") (pintype "passive"))
      (node (ref "C22") (pin "2") (pinfunction "2_2") (pintype "passive"))
      (node (ref "C23") (pin "2") (pinfunction "2_2") (pintype "passive"))
      (node (ref "C24") (pin "1") (pinfunction "1_1") (pintype "passive"))
      (node (ref "C25") (pin "1") (pinfunction "1_1") (pintype "passive"))
      (node (ref "C26") (pin "2") (pinfunction "2_2") (pintype "passive"))
      (node (ref "C27") (pin "1") (pinfunction "1_1") (pintype "passive"))
      (node (ref "C28") (pin "2") (pinfunction "2_2") (pintype "passive"))
      (node (ref "C3") (pin "2") (pinfunction "2_2") (pintype "passive"))
      (node (ref "C4") (pin "2") (pinfunction "2_2") (pintype "passive"))
      (node (ref "C5") (pin "2") (pinfunction "2_2") (pintype "passive"))
      (node (ref "C6") (pin "1") (pinfunction "1_1") (pintype "passive"))
      (node (ref "C7") (pin "1") (pinfunction "1_1") (pintype "passive"))
      (node (ref "C8") (pin "1") (pinfunction "1_1") (pintype "passive"))
      (node (ref "C9") (pin "2") (pinfunction "2_2") (pintype "passive"))
      (node (ref "D10") (pin "1") (pinfunction "K_1") (pintype "passive"))
      (node (ref "D11") (pin "1") (pinfunction "K_1") (pintype "passive"))
      (node (ref "D2") (pin "1") (pinfunction "1_1") (pintype "passive"))
      (node (ref "D5") (pin "1") (pinfunction "1_1") (pintype "passive"))
      (node (ref "D7") (pin "1") (pinfunction "K_1") (pintype "passive"))
      (node (ref "D8") (pin "1") (pinfunction "K_1") (pintype "passive"))
      (node (ref "D9") (pin "1") (pinfunction "K_1") (pintype "passive"))
      (node (ref "J1") (pin "5") (pinfunction "GND_5") (pintype "power_in"))
      (node (ref "J2") (pin "5") (pinfunction "GND_5") (pintype "power_in"))
      (node (ref "J4") (pin "3") (pinfunction "3_3") (pintype "passive"))
      (node (ref "J4") (pin "9") (pinfunction "9_9") (pintype "passive"))
      (node (ref "L4") (pin "1") (pinfunction "1_1") (pintype "passive"))
      (node (ref "P1") (pin "1") (pinfunction "1_1") (pintype "passive"))
      (node (ref "Q1") (pin "2") (pinfunction "E_2") (pintype "passive"))
      (node (ref "R11") (pin "2") (pinfunction "2_2") (pintype "passive"))
      (node (ref "R19") (pin "2") (pinfunction "2_2") (pintype "passive"))
      (node (ref "R2") (pin "2") (pinfunction "2_2") (pintype "passive"))
      (node (ref "R23") (pin "1") (pinfunction "1_1") (pintype "passive"))
      (node (ref "R26") (pin "2") (pinfunction "2_2") (pintype "passive"))
      (node (ref "R5") (pin "2") (pinfunction "2_2") (pintype "passive"))
      (node (ref "R7") (pin "1") (pinfunction "1_1") (pintype "passive"))
      (node (ref "U1") (pin "2") (pinfunction "VSS_2") (pintype "power_in"))
      (node (ref "U2") (pin "11") (pinfunction "GND_11") (pintype "passive"))
      (node (ref "U2") (pin "13") (pinfunction "GND_13") (pintype "passive"))
      (node (ref "U2") (pin "3") (pinfunction "PGND_3") (pintype "passive"))
      (node (ref "U3") (pin "23") (pinfunction "VSS_1_23") (pintype "power_in"))
      (node (ref "U3") (pin "35") (pinfunction "VSS_2_35") (pintype "power_in"))
      (node (ref "U3") (pin "47") (pinfunction "VSS_3_47") (pintype "power_in"))
      (node (ref "U3") (pin "8") (pinfunction "VSSA_8") (pintype "power_in"))
      (node (ref "U4") (pin "9") (pinfunction "GND_9") (pintype "passive"))
      (node (ref "U5") (pin "2") (pinfunction "COMM_2") (pintype "power_in"))
      (node (ref "U5") (pin "9") (pinfunction "EP_9") (pintype "power_in"))
      (node (ref "U6") (pin "12") (pinfunction "GND_12") (pintype "passive"))
      (node (ref "U6") (pin "13") (pinfunction "WAKEUP_13") (pintype "passive"))
      (node (ref "U6") (pin "21") (pinfunction "EP_GND_21") (pintype "passive"))
      (node (ref "U6") (pin "3") (pinfunction "GND_3") (pintype "passive"))
    )
    (net (code "30") (name "Net-(ANT1-RFOUT)") (class "Default")
      (node (ref "ANT1") (pin "2") (pinfunction "RFOUT_2") (pintype "passive"))
      (node (ref "C29") (pin "2") (pinfunction "2_2") (pintype "passive"))
    )
    (net (code "31") (name "Net-(C11-Pad1)") (class "Default")
      (node (ref "C11") (pin "1") (pinfunction "1_1") (pintype "passive"))
      (node (ref "C30") (pin "2") (pinfunction "2_2") (pintype "passive"))
    )
    (net (code "32") (name "Net-(C13-Pad2)") (class "Default")
      (node (ref "C13") (pin "2") (pinfunction "2_2") (pintype "passive"))
      (node (ref "C16") (pin "1") (pinfunction "1_1") (pintype "passive"))
      (node (ref "R5") (pin "1") (pinfunction "1_1") (pintype "passive"))
    )
    (net (code "33") (name "Net-(C14-Pad2)") (class "Default")
      (node (ref "C14") (pin "2") (pinfunction "2_2") (pintype "passive"))
      (node (ref "C15") (pin "2") (pinfunction "2_2") (pintype "passive"))
      (node (ref "L3") (pin "2") (pinfunction "2_2") (pintype "passive"))
      (node (ref "R4") (pin "1") (pinfunction "1_1") (pintype "passive"))
    )
    (net (code "34") (name "Net-(C27-Pad2)") (class "Default")
      (node (ref "C27") (pin "2") (pinfunction "2_2") (pintype "passive"))
      (node (ref "F1") (pin "2") (pinfunction "2_2") (pintype "passive"))
      (node (ref "R12") (pin "2") (pinfunction "2_2") (pintype "passive"))
    )
    (net (code "35") (name "Net-(C29-Pad1)") (class "Default")
      (node (ref "C29") (pin "1") (pinfunction "1_1") (pintype "passive"))
      (node (ref "C30") (pin "1") (pinfunction "1_1") (pintype "passive"))
      (node (ref "L4") (pin "2") (pinfunction "2_2") (pintype "passive"))
    )
    (net (code "36") (name "Net-(D1-C)") (class "Default")
      (node (ref "D1") (pin "1") (pinfunction "C_1") (pintype "passive"))
      (node (ref "R1") (pin "1") (pinfunction "1_1") (pintype "passive"))
    )
    (net (code "37") (name "Net-(D7-A)") (class "Default")
      (node (ref "D7") (pin "2") (pinfunction "A_2") (pintype "passive"))
      (node (ref "R14") (pin "2") (pinfunction "2_2") (pintype "passive"))
    )
    (net (code "38") (name "Net-(D8-A)") (class "Default")
      (node (ref "D8") (pin "2") (pinfunction "A_2") (pintype "passive"))
      (node (ref "R15") (pin "2") (pinfunction "2_2") (pintype "passive"))
    )
    (net (code "39") (name "Net-(D9-A)") (class "Default")
      (node (ref "D9") (pin "2") (pinfunction "A_2") (pintype "passive"))
      (node (ref "R16") (pin "2") (pinfunction "2_2") (pintype "passive"))
    )
    (net (code "40") (name "Net-(D10-A)") (class "Default")
      (node (ref "D10") (pin "2") (pinfunction "A_2") (pintype "passive"))
      (node (ref "R17") (pin "2") (pinfunction "2_2") (pintype "passive"))
    )
    (net (code "41") (name "Net-(D11-A)") (class "Default")
      (node (ref "D11") (pin "2") (pinfunction "A_2") (pintype "passive"))
      (node (ref "R18") (pin "2") (pinfunction "2_2") (pintype "passive"))
    )
    (net (code "42") (name "Net-(J2-VBUS)") (class "Default")
      (node (ref "D5") (pin "4") (pinfunction "4_4") (pintype "passive"))
      (node (ref "J2") (pin "1") (pinfunction "VBUS_1") (pintype "power_in"))
      (node (ref "R20") (pin "1") (pinfunction "1_1") (pintype "passive"))
    )
    (net (code "43") (name "Net-(Q1-B)") (class "Default")
      (node (ref "Q1") (pin "1") (pinfunction "B_1") (pintype "passive"))
      (node (ref "R13") (pin "2") (pinfunction "2_2") (pintype "passive"))
    )
    (net (code "44") (name "Net-(Q1-C)") (class "Default")
      (node (ref "L2") (pin "1") (pinfunction "1_1") (pintype "passive"))
      (node (ref "LS1") (pin "16") (pinfunction "16_16") (pintype "passive"))
      (node (ref "Q1") (pin "3") (pinfunction "C_3") (pintype "passive"))
    )
    (net (code "45") (name "Net-(U1-PROG)") (class "Default")
      (node (ref "R2") (pin "1") (pinfunction "1_1") (pintype "passive"))
      (node (ref "U1") (pin "5") (pinfunction "PROG_5") (pintype "passive"))
    )
    (net (code "46") (name "Net-(U1-STAT)") (class "Default")
      (node (ref "R1") (pin "2") (pinfunction "2_2") (pintype "passive"))
      (node (ref "U1") (pin "1") (pinfunction "STAT_1") (pintype "open_collector"))
    )
    (net (code "47") (name "Net-(U1-VBAT)") (class "Default")
      (node (ref "BT1") (pin "2") (pinfunction "2_2") (pintype "passive"))
      (node (ref "C2") (pin "1") (pinfunction "1_1") (pintype "passive"))
      (node (ref "SW1") (pin "2") (pinfunction "2_2") (pintype "passive"))
      (node (ref "U1") (pin "3") (pinfunction "VBAT_3") (pintype "power_in"))
    )
    (net (code "48") (name "Net-(U2-EN)") (class "Default")
      (node (ref "C3") (pin "1") (pinfunction "1_1") (pintype "passive"))
      (node (ref "R25") (pin "1") (pinfunction "1_1") (pintype "passive"))
      (node (ref "SW1") (pin "1") (pinfunction "1_1") (pintype "passive"))
      (node (ref "U2") (pin "10") (pinfunction "MODE_10") (pintype "passive"))
      (node (ref "U2") (pin "5") (pinfunction "PVIN_5") (pintype "passive"))
      (node (ref "U2") (pin "6") (pinfunction "VIN_6") (pintype "passive"))
      (node (ref "U2") (pin "9") (pinfunction "EN_9") (pintype "passive"))
    )
    (net (code "49") (name "Net-(U2-LX1)") (class "Default")
      (node (ref "L1") (pin "1") (pinfunction "1_1") (pintype "passive"))
      (node (ref "U2") (pin "4") (pinfunction "LX1_4") (pintype "passive"))
    )
    (net (code "50") (name "Net-(U2-LX2)") (class "Default")
      (node (ref "L1") (pin "2") (pinfunction "2_2") (pintype "passive"))
      (node (ref "U2") (pin "2") (pinfunction "LX2_2") (pintype "passive"))
    )
    (net (code "51") (name "Net-(U3A-BOOT0)") (class "Default")
      (node (ref "R11") (pin "1") (pinfunction "1_1") (pintype "passive"))
      (node (ref "U3") (pin "44") (pinfunction "BOOT0_44") (pintype "input"))
    )
    (net (code "52") (name "Net-(U3A-PD0-OSC_IN)") (class "Default")
      (node (ref "C28") (pin "1") (pinfunction "1_1") (pintype "passive"))
      (node (ref "F1") (pin "1") (pinfunction "1_1") (pintype "passive"))
      (node (ref "U3") (pin "5") (pinfunction "PD0-OSC_IN_5") (pintype "bidirectional"))
    )
    (net (code "53") (name "Net-(U3A-PD1-OSC_OUT)") (class "Default")
      (node (ref "R12") (pin "1") (pinfunction "1_1") (pintype "passive"))
      (node (ref "U3") (pin "6") (pinfunction "PD1-OSC_OUT_6") (pintype "bidirectional"))
    )
    (net (code "54") (name "Net-(U4-RFIN)") (class "Default")
      (node (ref "C11") (pin "2") (pinfunction "2_2") (pintype "passive"))
      (node (ref "U4") (pin "2") (pinfunction "RFIN_2") (pintype "passive"))
    )
    (net (code "55") (name "Net-(U4-RFOUT)") (class "Default")
      (node (ref "C13") (pin "1") (pinfunction "1_1") (pintype "passive"))
      (node (ref "L3") (pin "1") (pinfunction "1_1") (pintype "passive"))
      (node (ref "U4") (pin "7") (pinfunction "RFOUT_7") (pintype "passive"))
    )
    (net (code "56") (name "Net-(U4-VCC)") (class "Default")
      (node (ref "C12") (pin "2") (pinfunction "2_2") (pintype "passive"))
      (node (ref "R3") (pin "1") (pinfunction "1_1") (pintype "passive"))
      (node (ref "U4") (pin "1") (pinfunction "VCC_1") (pintype "passive"))
    )
    (net (code "57") (name "Net-(U5-CLPF)") (class "Default")
      (node (ref "C20") (pin "2") (pinfunction "2_2") (pintype "passive"))
      (node (ref "U5") (pin "3") (pinfunction "CLPF_3") (pintype "passive"))
    )
    (net (code "58") (name "Net-(U5-INHI)") (class "Default")
      (node (ref "C16") (pin "2") (pinfunction "2_2") (pintype "passive"))
      (node (ref "U5") (pin "1") (pinfunction "INHI_1") (pintype "input"))
    )
    (net (code "59") (name "Net-(U5-INLO)") (class "Default")
      (node (ref "C17") (pin "2") (pinfunction "2_2") (pintype "passive"))
      (node (ref "U5") (pin "8") (pinfunction "INLO_8") (pintype "input"))
    )
    (net (code "60") (name "Net-(U5-TADJ)") (class "Default")
      (node (ref "R7") (pin "2") (pinfunction "2_2") (pintype "passive"))
      (node (ref "U5") (pin "6") (pinfunction "TADJ_6") (pintype "input"))
    )
    (net (code "61") (name "Net-(U5-VOUT)") (class "Default")
      (node (ref "R8") (pin "2") (pinfunction "2_2") (pintype "passive"))
      (node (ref "R9") (pin "1") (pinfunction "1_1") (pintype "passive"))
      (node (ref "U5") (pin "5") (pinfunction "VOUT_5") (pintype "output"))
    )
    (net (code "62") (name "Net-(U5-VPOS)") (class "Default")
      (node (ref "C18") (pin "1") (pinfunction "1_1") (pintype "passive"))
      (node (ref "C19") (pin "1") (pinfunction "1_1") (pintype "passive"))
      (node (ref "R6") (pin "1") (pinfunction "1_1") (pintype "passive"))
      (node (ref "U5") (pin "7") (pinfunction "VPOS_7") (pintype "power_in"))
    )
    (net (code "63") (name "Net-(U5-VSET)") (class "Default")
      (node (ref "R8") (pin "1") (pinfunction "1_1") (pintype "passive"))
      (node (ref "U5") (pin "4") (pinfunction "VSET_4") (pintype "input"))
    )
    (net (code "64") (name "Net-(U6-VBUS)") (class "Default")
      (node (ref "R22") (pin "1") (pinfunction "1_1") (pintype "passive"))
      (node (ref "R23") (pin "2") (pinfunction "2_2") (pintype "passive"))
      (node (ref "U6") (pin "8") (pinfunction "VBUS_8") (pintype "passive"))
    )
    (net (code "65") (name "Net-(U6-VDD)") (class "Default")
      (node (ref "C23") (pin "1") (pinfunction "1_1") (pintype "passive"))
      (node (ref "C24") (pin "2") (pinfunction "2_2") (pintype "passive"))
      (node (ref "R24") (pin "1") (pinfunction "1_1") (pintype "passive"))
      (node (ref "U6") (pin "6") (pinfunction "VDD_6") (pintype "passive"))
    )
    (net (code "66") (name "unconnected-(ANT1-GND-Pad1)") (class "Default")
      (node (ref "ANT1") (pin "1") (pinfunction "GND_1") (pintype "passive"))
    )
    (net (code "67") (name "unconnected-(ANT1-GND-Pad3)") (class "Default")
      (node (ref "ANT1") (pin "3") (pinfunction "GND_3") (pintype "passive"))
    )
    (net (code "68") (name "unconnected-(ANT1-MNT-Pad4)") (class "Default")
      (node (ref "ANT1") (pin "4") (pinfunction "MNT_4") (pintype "passive"))
    )
    (net (code "69") (name "unconnected-(J1-ID-Pad4)") (class "Default")
      (node (ref "J1") (pin "4") (pinfunction "ID_4") (pintype "bidirectional+no_connect"))
    )
    (net (code "70") (name "unconnected-(J1-SHIELD-PadS1)") (class "Default")
      (node (ref "J1") (pin "S1") (pinfunction "SHIELD_S1") (pintype "passive+no_connect"))
    )
    (net (code "71") (name "unconnected-(J1-SHIELD-PadS2)") (class "Default")
      (node (ref "J1") (pin "S2") (pinfunction "SHIELD_S2") (pintype "passive+no_connect"))
    )
    (net (code "72") (name "unconnected-(J1-SHIELD-PadS3)") (class "Default")
      (node (ref "J1") (pin "S3") (pinfunction "SHIELD_S3") (pintype "passive+no_connect"))
    )
    (net (code "73") (name "unconnected-(J1-SHIELD-PadS4)") (class "Default")
      (node (ref "J1") (pin "S4") (pinfunction "SHIELD_S4") (pintype "passive+no_connect"))
    )
    (net (code "74") (name "unconnected-(J1-SHIELD-PadS5)") (class "Default")
      (node (ref "J1") (pin "S5") (pinfunction "SHIELD_S5") (pintype "passive+no_connect"))
    )
    (net (code "75") (name "unconnected-(J1-SHIELD-PadS6)") (class "Default")
      (node (ref "J1") (pin "S6") (pinfunction "SHIELD_S6") (pintype "passive+no_connect"))
    )
    (net (code "76") (name "unconnected-(J2-ID-Pad4)") (class "Default")
      (node (ref "J2") (pin "4") (pinfunction "ID_4") (pintype "bidirectional+no_connect"))
    )
    (net (code "77") (name "unconnected-(J2-SHIELD-PadS1)") (class "Default")
      (node (ref "J2") (pin "S1") (pinfunction "SHIELD_S1") (pintype "passive+no_connect"))
    )
    (net (code "78") (name "unconnected-(J2-SHIELD-PadS2)") (class "Default")
      (node (ref "J2") (pin "S2") (pinfunction "SHIELD_S2") (pintype "passive+no_connect"))
    )
    (net (code "79") (name "unconnected-(J2-SHIELD-PadS3)") (class "Default")
      (node (ref "J2") (pin "S3") (pinfunction "SHIELD_S3") (pintype "passive+no_connect"))
    )
    (net (code "80") (name "unconnected-(J2-SHIELD-PadS4)") (class "Default")
      (node (ref "J2") (pin "S4") (pinfunction "SHIELD_S4") (pintype "passive+no_connect"))
    )
    (net (code "81") (name "unconnected-(J2-SHIELD-PadS5)") (class "Default")
      (node (ref "J2") (pin "S5") (pinfunction "SHIELD_S5") (pintype "passive+no_connect"))
    )
    (net (code "82") (name "unconnected-(J2-SHIELD-PadS6)") (class "Default")
      (node (ref "J2") (pin "S6") (pinfunction "SHIELD_S6") (pintype "passive+no_connect"))
    )
    (net (code "83") (name "unconnected-(J4-Pad5)") (class "Default")
      (node (ref "J4") (pin "5") (pinfunction "5_5") (pintype "passive+no_connect"))
    )
    (net (code "84") (name "unconnected-(J4-Pad7)") (class "Default")
      (node (ref "J4") (pin "7") (pinfunction "7_7") (pintype "passive+no_connect"))
    )
    (net (code "85") (name "unconnected-(SW1-MNT_1-Pad5)") (class "Default")
      (node (ref "SW1") (pin "5") (pinfunction "MNT_1_5") (pintype "passive"))
    )
    (net (code "86") (name "unconnected-(SW1-MNT_2-Pad6)") (class "Default")
      (node (ref "SW1") (pin "6") (pinfunction "MNT_2_6") (pintype "passive"))
    )
    (net (code "87") (name "unconnected-(SW1-Pad3)") (class "Default")
      (node (ref "SW1") (pin "3") (pinfunction "3_3") (pintype "passive"))
    )
    (net (code "88") (name "unconnected-(SW1-Pad4)") (class "Default")
      (node (ref "SW1") (pin "4") (pinfunction "4_4") (pintype "passive"))
    )
    (net (code "89") (name "unconnected-(U2-PG-Pad7)") (class "Default")
      (node (ref "U2") (pin "7") (pinfunction "PG_7") (pintype "passive"))
    )
    (net (code "90") (name "unconnected-(U2-~{BAT}-Pad8)") (class "Default")
      (node (ref "U2") (pin "8") (pinfunction "~{BAT}_8") (pintype "passive"))
    )
    (net (code "91") (name "unconnected-(U3A-PA0-WKUP-Pad10)") (class "Default")
      (node (ref "U3") (pin "10") (pinfunction "PA0-WKUP_10") (pintype "bidirectional"))
    )
    (net (code "92") (name "unconnected-(U3A-PA3-Pad13)") (class "Default")
      (node (ref "U3") (pin "13") (pinfunction "PA3_13") (pintype "bidirectional"))
    )
    (net (code "93") (name "unconnected-(U3A-PA4-Pad14)") (class "Default")
      (node (ref "U3") (pin "14") (pinfunction "PA4_14") (pintype "bidirectional"))
    )
    (net (code "94") (name "unconnected-(U3A-PA5-Pad15)") (class "Default")
      (node (ref "U3") (pin "15") (pinfunction "PA5_15") (pintype "bidirectional"))
    )
    (net (code "95") (name "unconnected-(U3A-PA6-Pad16)") (class "Default")
      (node (ref "U3") (pin "16") (pinfunction "PA6_16") (pintype "bidirectional"))
    )
    (net (code "96") (name "unconnected-(U3A-PA7-Pad17)") (class "Default")
      (node (ref "U3") (pin "17") (pinfunction "PA7_17") (pintype "bidirectional"))
    )
    (net (code "97") (name "unconnected-(U3A-PA8-Pad29)") (class "Default")
      (node (ref "U3") (pin "29") (pinfunction "PA8_29") (pintype "bidirectional"))
    )
    (net (code "98") (name "unconnected-(U3A-PB0-Pad18)") (class "Default")
      (node (ref "U3") (pin "18") (pinfunction "PB0_18") (pintype "bidirectional"))
    )
    (net (code "99") (name "unconnected-(U3A-PB2-Pad20)") (class "Default")
      (node (ref "U3") (pin "20") (pinfunction "PB2_20") (pintype "bidirectional"))
    )
    (net (code "100") (name "unconnected-(U3A-PB12-Pad25)") (class "Default")
      (node (ref "U3") (pin "25") (pinfunction "PB12_25") (pintype "bidirectional"))
    )
    (net (code "101") (name "unconnected-(U3A-PC13-TAMPER-RTC-Pad2)") (class "Default")
      (node (ref "U3") (pin "2") (pinfunction "PC13-TAMPER-RTC_2") (pintype "bidirectional"))
    )
    (net (code "102") (name "unconnected-(U3A-PC14-OSC32_IN-Pad3)") (class "Default")
      (node (ref "U3") (pin "3") (pinfunction "PC14-OSC32_IN_3") (pintype "bidirectional"))
    )
    (net (code "103") (name "unconnected-(U3A-PC15-OSC32_OUT-Pad4)") (class "Default")
      (node (ref "U3") (pin "4") (pinfunction "PC15-OSC32_OUT_4") (pintype "bidirectional"))
    )
    (net (code "104") (name "unconnected-(U3B-VBAT-Pad1)") (class "Default")
      (node (ref "U3") (pin "1") (pinfunction "VBAT_1") (pintype "power_in+no_connect"))
    )
    (net (code "105") (name "unconnected-(U6-GPIO.0{slash}CLK-Pad2)") (class "Default")
      (node (ref "U6") (pin "2") (pinfunction "GPIO.0/CLK_2") (pintype "passive+no_connect"))
    )
    (net (code "106") (name "unconnected-(U6-GPIO.1{slash}RS485-Pad1)") (class "Default")
      (node (ref "U6") (pin "1") (pinfunction "GPIO.1/RS485_1") (pintype "passive+no_connect"))
    )
    (net (code "107") (name "unconnected-(U6-GPIO.2{slash}TXT-Pad20)") (class "Default")
      (node (ref "U6") (pin "20") (pinfunction "GPIO.2/TXT_20") (pintype "passive+no_connect"))
    )
    (net (code "108") (name "unconnected-(U6-GPIO.3{slash}RXT-Pad19)") (class "Default")
      (node (ref "U6") (pin "19") (pinfunction "GPIO.3/RXT_19") (pintype "passive+no_connect"))
    )
    (net (code "109") (name "unconnected-(U6-SUSPENDb-Pad11)") (class "Default")
      (node (ref "U6") (pin "11") (pinfunction "SUSPENDb_11") (pintype "passive+no_connect"))
    )
  )
)
